# FLC100_remote_v1_1.net
KiCad netlist of a schematic drawn in EAGLE
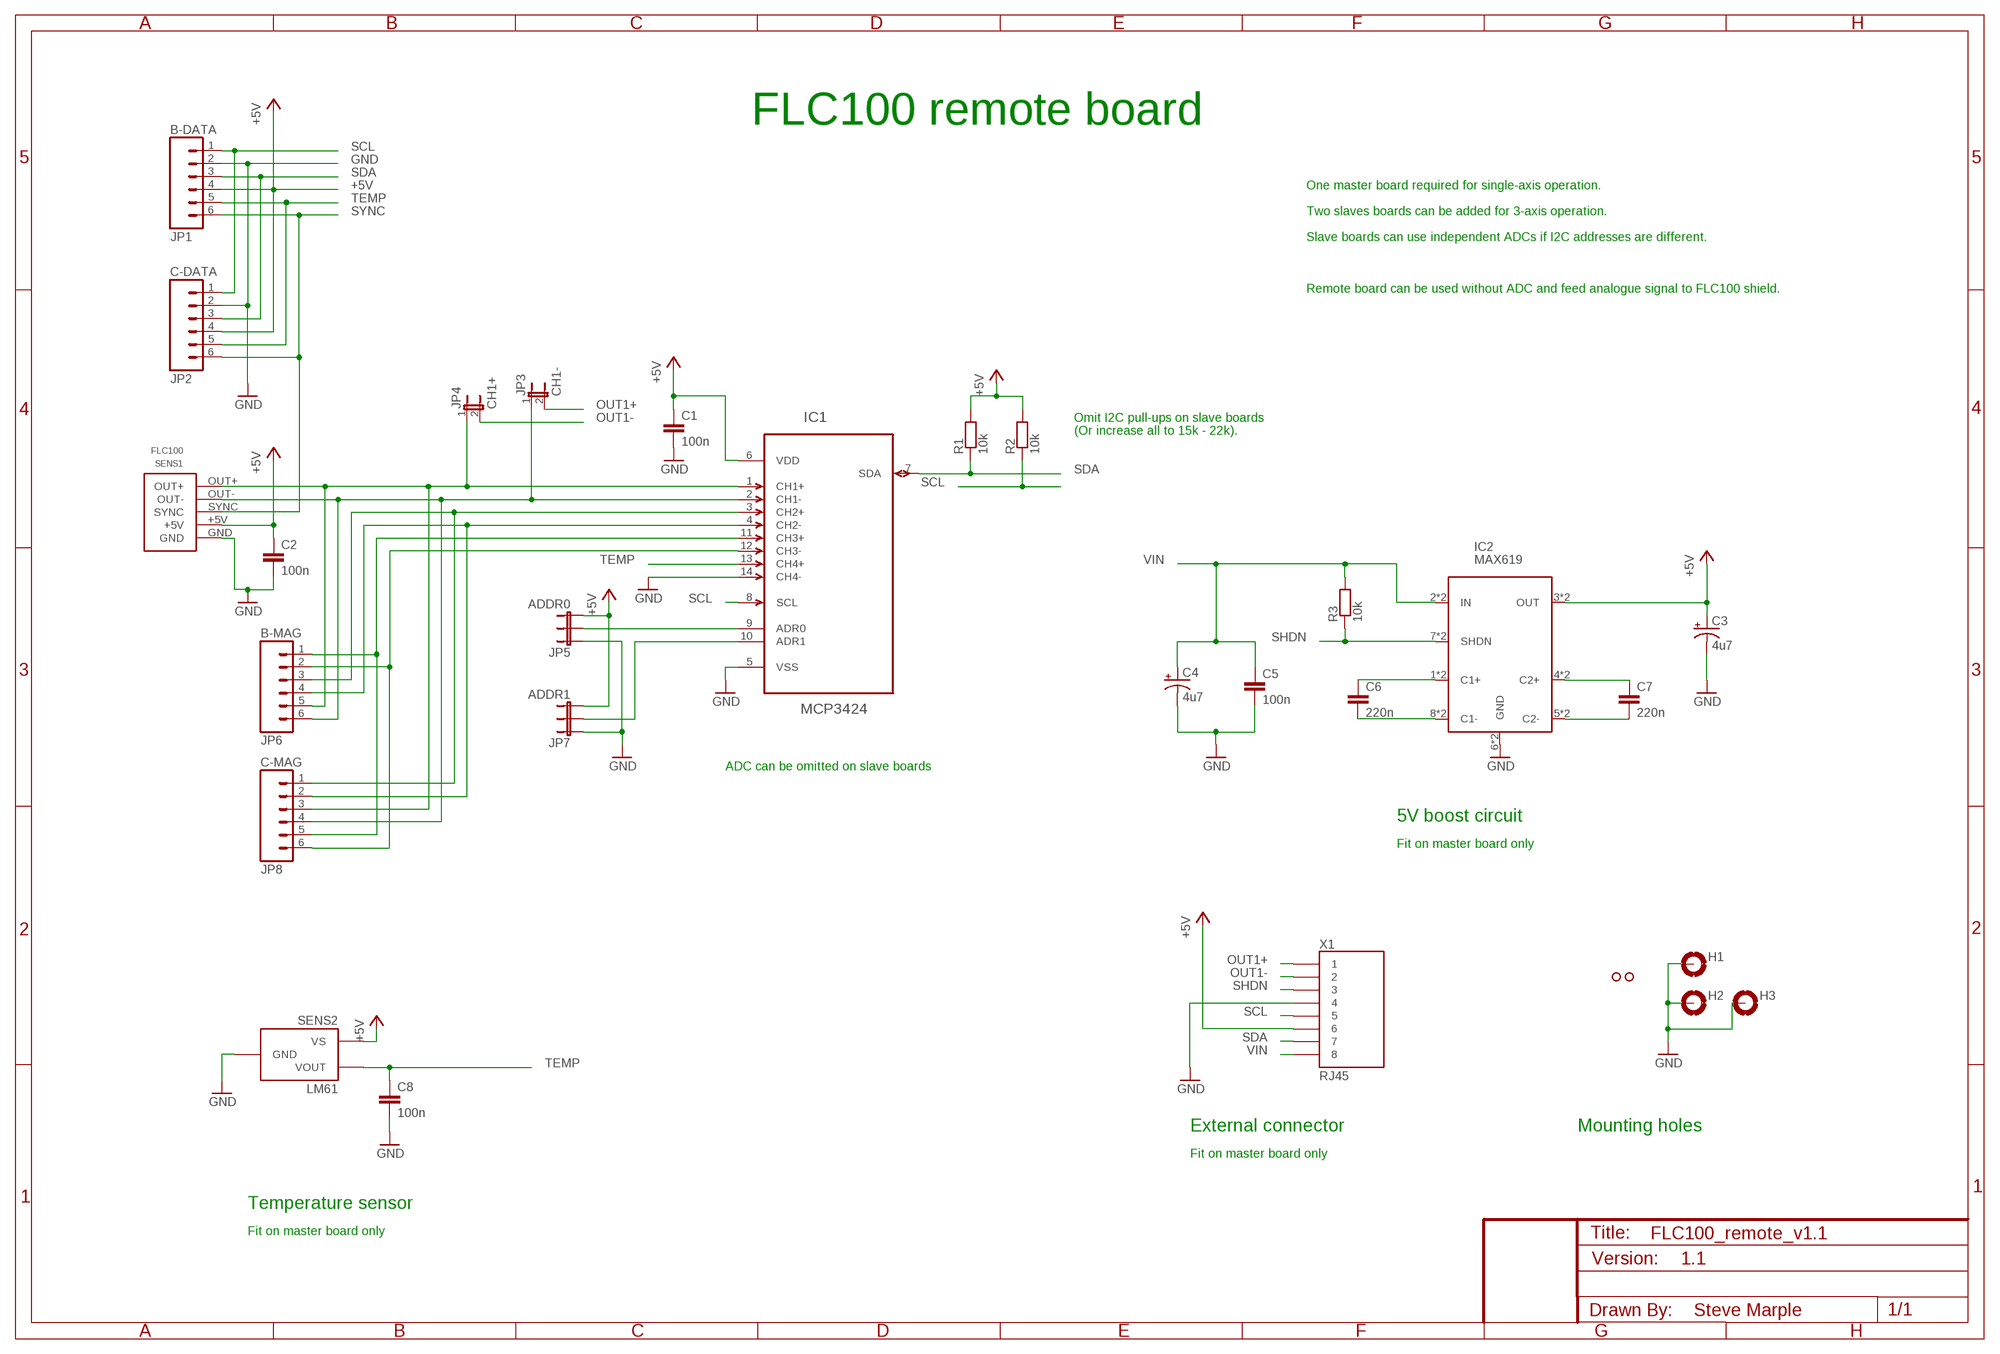
[diagram p0: schematic, sheet 1]

(export (version "E")
  (design (tool "Eeschema 10.0.6"))
  (components
    (comp (ref "C1")
      (value "100n")
      (footprint "eagle-import:CAP-PTH-SMALL")
      (libsource (lib "eagle-import") (part "CAPPTH"))
    )
    (comp (ref "C2")
      (value "100n")
      (footprint "eagle-import:CAP-PTH-SMALL")
      (libsource (lib "eagle-import") (part "CAPPTH"))
    )
    (comp (ref "C3")
      (value "4u7")
      (footprint "eagle-import:CPOL-RADIAL-10UF-25V")
      (libsource (lib "eagle-import") (part "CAP_POLPTH2"))
    )
    (comp (ref "C4")
      (value "4u7")
      (footprint "eagle-import:CPOL-RADIAL-10UF-25V")
      (libsource (lib "eagle-import") (part "CAP_POLPTH2"))
    )
    (comp (ref "C5")
      (value "100n")
      (footprint "eagle-import:CAP-PTH-SMALL")
      (libsource (lib "eagle-import") (part "CAPPTH"))
    )
    (comp (ref "C6")
      (value "220n")
      (footprint "eagle-import:CAP-PTH-5MM")
      (libsource (lib "eagle-import") (part "CAPPTH1"))
    )
    (comp (ref "C7")
      (value "220n")
      (footprint "eagle-import:CAP-PTH-5MM")
      (libsource (lib "eagle-import") (part "CAPPTH1"))
    )
    (comp (ref "C8")
      (value "100n")
      (footprint "eagle-import:CAP-PTH-SMALL")
      (libsource (lib "eagle-import") (part "CAPPTH"))
    )
    (comp (ref "H1")
      (value "MOUNT-PAD-ROUND3.0")
      (footprint "eagle-import:3,0-PAD")
      (libsource (lib "eagle-import") (part "MOUNT-PAD-ROUND3.0"))
    )
    (comp (ref "H2")
      (value "MOUNT-PAD-ROUND3.0")
      (footprint "eagle-import:3,0-PAD")
      (libsource (lib "eagle-import") (part "MOUNT-PAD-ROUND3.0"))
    )
    (comp (ref "H3")
      (value "MOUNT-PAD-ROUND3.0")
      (footprint "eagle-import:3,0-PAD")
      (libsource (lib "eagle-import") (part "MOUNT-PAD-ROUND3.0"))
    )
    (comp (ref "IC1")
      (value "MCP3424")
      (footprint "eagle-import:SOIC127P600X175-14N")
      (fields (field (name "MPN") "MCP3424-E/SL"))
      (libsource (lib "eagle-import") (part "MCP3424-E/SL"))
    )
    (comp (ref "IC2")
      (value "MAX619")
      (footprint "eagle-import:DIL08-SOIC8")
      (libsource (lib "eagle-import") (part "MAX619DIL08/SOIC8"))
    )
    (comp (ref "JP1")
      (value "B-DATA")
      (footprint "eagle-import:1X06_FEMALE")
      (libsource (lib "eagle-import") (part "M06FEMALE"))
    )
    (comp (ref "JP2")
      (value "C-DATA")
      (footprint "eagle-import:1X06_FEMALE")
      (libsource (lib "eagle-import") (part "M06FEMALE"))
    )
    (comp (ref "JP3")
      (value "CH1-")
      (footprint "eagle-import:1X02")
      (libsource (lib "eagle-import") (part "JUMPER-2PTH"))
    )
    (comp (ref "JP4")
      (value "CH1+")
      (footprint "eagle-import:1X02")
      (libsource (lib "eagle-import") (part "JUMPER-2PTH"))
    )
    (comp (ref "JP5")
      (value "ADDR0")
      (footprint "eagle-import:1X03")
      (libsource (lib "eagle-import") (part "JUMPER-3PTH"))
    )
    (comp (ref "JP6")
      (value "B-MAG")
      (footprint "eagle-import:1X06_FEMALE")
      (libsource (lib "eagle-import") (part "M06FEMALE"))
    )
    (comp (ref "JP7")
      (value "ADDR1")
      (footprint "eagle-import:1X03")
      (libsource (lib "eagle-import") (part "JUMPER-3PTH"))
    )
    (comp (ref "JP8")
      (value "C-MAG")
      (footprint "eagle-import:1X06_FEMALE")
      (libsource (lib "eagle-import") (part "M06FEMALE"))
    )
    (comp (ref "R1")
      (value "10k")
      (footprint "eagle-import:RES-AXIAL-0.4")
      (libsource (lib "eagle-import") (part "RESISTOR"))
    )
    (comp (ref "R2")
      (value "10k")
      (footprint "eagle-import:RES-AXIAL-0.4")
      (libsource (lib "eagle-import") (part "RESISTOR"))
    )
    (comp (ref "R3")
      (value "10k")
      (footprint "eagle-import:RES-AXIAL-0.4")
      (libsource (lib "eagle-import") (part "RESISTOR"))
    )
    (comp (ref "SENS1")
      (value "FLC100")
      (footprint "eagle-import:FLC100")
      (libsource (lib "eagle-import") (part "FLC100"))
    )
    (comp (ref "SENS2")
      (value "LM61")
      (footprint "eagle-import:TO-92")
      (libsource (lib "eagle-import") (part "LM61"))
    )
    (comp (ref "U$1")
      (value "PAD")
      (footprint "eagle-import:PAD")
      (libsource (lib "eagle-import") (part "PAD"))
    )
    (comp (ref "U$2")
      (value "PAD")
      (footprint "eagle-import:PAD")
      (libsource (lib "eagle-import") (part "PAD"))
    )
    (comp (ref "X1")
      (value "RJ45")
      (footprint "eagle-import:RJ45-8")
      (libsource (lib "eagle-import") (part "RJ45-8PTH"))
    )
  )
  (nets
    (net (code "1") (name "+5V") (class "Default")
      (node (ref "C1") (pin "1") (pinfunction "1_1") (pintype "passive"))
      (node (ref "C2") (pin "1") (pinfunction "1_1") (pintype "passive"))
      (node (ref "C3") (pin "1") (pinfunction "+_1") (pintype "passive"))
      (node (ref "IC1") (pin "6") (pinfunction "VDD_6") (pintype "power_in"))
      (node (ref "IC2") (pin "3") (pinfunction "OUT_3") (pintype "power_in"))
      (node (ref "IC2") (pin "3@1") (pinfunction "OUT_3@1") (pintype "power_in"))
      (node (ref "JP1") (pin "4") (pinfunction "4_4") (pintype "passive"))
      (node (ref "JP2") (pin "4") (pinfunction "4_4") (pintype "passive"))
      (node (ref "JP5") (pin "3") (pinfunction "3_3") (pintype "passive"))
      (node (ref "JP7") (pin "3") (pinfunction "3_3") (pintype "passive"))
      (node (ref "R1") (pin "P$2") (pinfunction "2_P$2") (pintype "passive"))
      (node (ref "R2") (pin "P$2") (pinfunction "2_P$2") (pintype "passive"))
      (node (ref "SENS1") (pin "+5V") (pinfunction "+5V_+5V") (pintype "power_in"))
      (node (ref "SENS2") (pin "1") (pinfunction "VS_1") (pintype "bidirectional"))
      (node (ref "X1") (pin "6") (pinfunction "6_6") (pintype "bidirectional"))
    )
    (net (code "2") (name "/OUT1+") (class "Default")
      (node (ref "JP3") (pin "2") (pinfunction "2_2") (pintype "passive"))
      (node (ref "X1") (pin "1") (pinfunction "1_1") (pintype "bidirectional"))
    )
    (net (code "3") (name "/OUT1-") (class "Default")
      (node (ref "JP4") (pin "2") (pinfunction "2_2") (pintype "passive"))
      (node (ref "X1") (pin "2") (pinfunction "2_2") (pintype "bidirectional"))
    )
    (net (code "4") (name "/SCL") (class "Default")
      (node (ref "IC1") (pin "8") (pinfunction "SCL_8") (pintype "input"))
      (node (ref "JP1") (pin "1") (pinfunction "1_1") (pintype "passive"))
      (node (ref "JP2") (pin "1") (pinfunction "1_1") (pintype "passive"))
      (node (ref "R2") (pin "P$1") (pinfunction "1_P$1") (pintype "passive"))
      (node (ref "X1") (pin "5") (pinfunction "5_5") (pintype "bidirectional"))
    )
    (net (code "5") (name "/SDA") (class "Default")
      (node (ref "IC1") (pin "7") (pinfunction "SDA_7") (pintype "bidirectional"))
      (node (ref "JP1") (pin "3") (pinfunction "3_3") (pintype "passive"))
      (node (ref "JP2") (pin "3") (pinfunction "3_3") (pintype "passive"))
      (node (ref "R1") (pin "P$1") (pinfunction "1_P$1") (pintype "passive"))
      (node (ref "X1") (pin "7") (pinfunction "7_7") (pintype "bidirectional"))
    )
    (net (code "6") (name "/SHDN") (class "Default")
      (node (ref "IC2") (pin "7") (pinfunction "SHDN_7") (pintype "input"))
      (node (ref "IC2") (pin "7@1") (pinfunction "SHDN_7@1") (pintype "input"))
      (node (ref "R3") (pin "P$1") (pinfunction "1_P$1") (pintype "passive"))
      (node (ref "X1") (pin "3") (pinfunction "3_3") (pintype "bidirectional"))
    )
    (net (code "7") (name "/SYNC") (class "Default")
      (node (ref "JP1") (pin "6") (pinfunction "6_6") (pintype "passive"))
      (node (ref "JP2") (pin "6") (pinfunction "6_6") (pintype "passive"))
      (node (ref "SENS1") (pin "SYNC") (pinfunction "SYNC_SYNC") (pintype "bidirectional"))
    )
    (net (code "8") (name "/TEMP") (class "Default")
      (node (ref "C8") (pin "1") (pinfunction "1_1") (pintype "passive"))
      (node (ref "IC1") (pin "13") (pinfunction "CH4+_13") (pintype "input"))
      (node (ref "JP1") (pin "5") (pinfunction "5_5") (pintype "passive"))
      (node (ref "JP2") (pin "5") (pinfunction "5_5") (pintype "passive"))
      (node (ref "SENS2") (pin "2") (pinfunction "VOUT_2") (pintype "bidirectional"))
    )
    (net (code "9") (name "/VIN") (class "Default")
      (node (ref "C4") (pin "1") (pinfunction "+_1") (pintype "passive"))
      (node (ref "C5") (pin "1") (pinfunction "1_1") (pintype "passive"))
      (node (ref "IC2") (pin "2") (pinfunction "IN_2") (pintype "power_in"))
      (node (ref "IC2") (pin "2@1") (pinfunction "IN_2@1") (pintype "power_in"))
      (node (ref "R3") (pin "P$2") (pinfunction "2_P$2") (pintype "passive"))
      (node (ref "X1") (pin "8") (pinfunction "8_8") (pintype "bidirectional"))
    )
    (net (code "10") (name "GND") (class "Default")
      (node (ref "C1") (pin "2") (pinfunction "2_2") (pintype "passive"))
      (node (ref "C2") (pin "2") (pinfunction "2_2") (pintype "passive"))
      (node (ref "C3") (pin "2") (pinfunction "-_2") (pintype "passive"))
      (node (ref "C4") (pin "2") (pinfunction "-_2") (pintype "passive"))
      (node (ref "C5") (pin "2") (pinfunction "2_2") (pintype "passive"))
      (node (ref "C8") (pin "2") (pinfunction "2_2") (pintype "passive"))
      (node (ref "H1") (pin "B3,0") (pinfunction "MOUNT_B3,0") (pintype "passive"))
      (node (ref "H2") (pin "B3,0") (pinfunction "MOUNT_B3,0") (pintype "passive"))
      (node (ref "H3") (pin "B3,0") (pinfunction "MOUNT_B3,0") (pintype "passive"))
      (node (ref "IC1") (pin "14") (pinfunction "CH4-_14") (pintype "input"))
      (node (ref "IC1") (pin "5") (pinfunction "VSS_5") (pintype "power_in"))
      (node (ref "IC2") (pin "6") (pinfunction "GND_6") (pintype "power_in"))
      (node (ref "IC2") (pin "6@1") (pinfunction "GND_6@1") (pintype "power_in"))
      (node (ref "JP1") (pin "2") (pinfunction "2_2") (pintype "passive"))
      (node (ref "JP2") (pin "2") (pinfunction "2_2") (pintype "passive"))
      (node (ref "JP5") (pin "1") (pinfunction "1_1") (pintype "passive"))
      (node (ref "JP7") (pin "1") (pinfunction "1_1") (pintype "passive"))
      (node (ref "SENS1") (pin "GND") (pinfunction "GND_GND") (pintype "power_in"))
      (node (ref "SENS2") (pin "3") (pinfunction "GND_3") (pintype "bidirectional"))
      (node (ref "X1") (pin "4") (pinfunction "4_4") (pintype "bidirectional"))
    )
    (net (code "11") (name "Net-(C6-Pad1)") (class "Default")
      (node (ref "C6") (pin "1") (pinfunction "1_1") (pintype "passive"))
      (node (ref "IC2") (pin "1") (pinfunction "C1+_1") (pintype "bidirectional"))
      (node (ref "IC2") (pin "1@1") (pinfunction "C1+_1@1") (pintype "bidirectional"))
    )
    (net (code "12") (name "Net-(C6-Pad2)") (class "Default")
      (node (ref "C6") (pin "2") (pinfunction "2_2") (pintype "passive"))
      (node (ref "IC2") (pin "8") (pinfunction "C1-_8") (pintype "bidirectional"))
      (node (ref "IC2") (pin "8@1") (pinfunction "C1-_8@1") (pintype "bidirectional"))
    )
    (net (code "13") (name "Net-(C7-Pad1)") (class "Default")
      (node (ref "C7") (pin "1") (pinfunction "1_1") (pintype "passive"))
      (node (ref "IC2") (pin "4") (pinfunction "C2+_4") (pintype "bidirectional"))
      (node (ref "IC2") (pin "4@1") (pinfunction "C2+_4@1") (pintype "bidirectional"))
    )
    (net (code "14") (name "Net-(C7-Pad2)") (class "Default")
      (node (ref "C7") (pin "2") (pinfunction "2_2") (pintype "passive"))
      (node (ref "IC2") (pin "5") (pinfunction "C2-_5") (pintype "bidirectional"))
      (node (ref "IC2") (pin "5@1") (pinfunction "C2-_5@1") (pintype "bidirectional"))
    )
    (net (code "15") (name "Net-(IC1-ADR0)") (class "Default")
      (node (ref "IC1") (pin "9") (pinfunction "ADR0_9") (pintype "input"))
      (node (ref "JP5") (pin "2") (pinfunction "2_2") (pintype "passive"))
    )
    (net (code "16") (name "Net-(IC1-ADR1)") (class "Default")
      (node (ref "IC1") (pin "10") (pinfunction "ADR1_10") (pintype "input"))
      (node (ref "JP7") (pin "2") (pinfunction "2_2") (pintype "passive"))
    )
    (net (code "17") (name "Net-(IC1-CH1+)") (class "Default")
      (node (ref "IC1") (pin "1") (pinfunction "CH1+_1") (pintype "input"))
      (node (ref "JP4") (pin "1") (pinfunction "1_1") (pintype "passive"))
      (node (ref "JP6") (pin "5") (pinfunction "5_5") (pintype "passive"))
      (node (ref "JP8") (pin "3") (pinfunction "3_3") (pintype "passive"))
      (node (ref "SENS1") (pin "OUT+") (pinfunction "OUT+_OUT+") (pintype "output"))
    )
    (net (code "18") (name "Net-(IC1-CH1-)") (class "Default")
      (node (ref "IC1") (pin "2") (pinfunction "CH1-_2") (pintype "input"))
      (node (ref "JP3") (pin "1") (pinfunction "1_1") (pintype "passive"))
      (node (ref "JP6") (pin "6") (pinfunction "6_6") (pintype "passive"))
      (node (ref "JP8") (pin "4") (pinfunction "4_4") (pintype "passive"))
      (node (ref "SENS1") (pin "OUT-") (pinfunction "OUT-_OUT-") (pintype "output"))
    )
    (net (code "19") (name "Net-(IC1-CH2+)") (class "Default")
      (node (ref "IC1") (pin "3") (pinfunction "CH2+_3") (pintype "input"))
      (node (ref "JP6") (pin "3") (pinfunction "3_3") (pintype "passive"))
      (node (ref "JP8") (pin "1") (pinfunction "1_1") (pintype "passive"))
    )
    (net (code "20") (name "Net-(IC1-CH2-)") (class "Default")
      (node (ref "IC1") (pin "4") (pinfunction "CH2-_4") (pintype "input"))
      (node (ref "JP6") (pin "4") (pinfunction "4_4") (pintype "passive"))
      (node (ref "JP8") (pin "2") (pinfunction "2_2") (pintype "passive"))
    )
    (net (code "21") (name "Net-(IC1-CH3+)") (class "Default")
      (node (ref "IC1") (pin "11") (pinfunction "CH3+_11") (pintype "input"))
      (node (ref "JP6") (pin "1") (pinfunction "1_1") (pintype "passive"))
      (node (ref "JP8") (pin "5") (pinfunction "5_5") (pintype "passive"))
    )
    (net (code "22") (name "Net-(IC1-CH3-)") (class "Default")
      (node (ref "IC1") (pin "12") (pinfunction "CH3-_12") (pintype "input"))
      (node (ref "JP6") (pin "2") (pinfunction "2_2") (pintype "passive"))
      (node (ref "JP8") (pin "6") (pinfunction "6_6") (pintype "passive"))
    )
    (net (code "23") (name "unconnected-(U$1-Pad1)") (class "Default")
      (node (ref "U$1") (pin "1") (pinfunction "1_1") (pintype "bidirectional"))
    )
    (net (code "24") (name "unconnected-(U$2-Pad1)") (class "Default")
      (node (ref "U$2") (pin "1") (pinfunction "1_1") (pintype "bidirectional"))
    )
  )
)
